# analog-encoder.net
KiCad netlist of a schematic drawn in Altium Designer
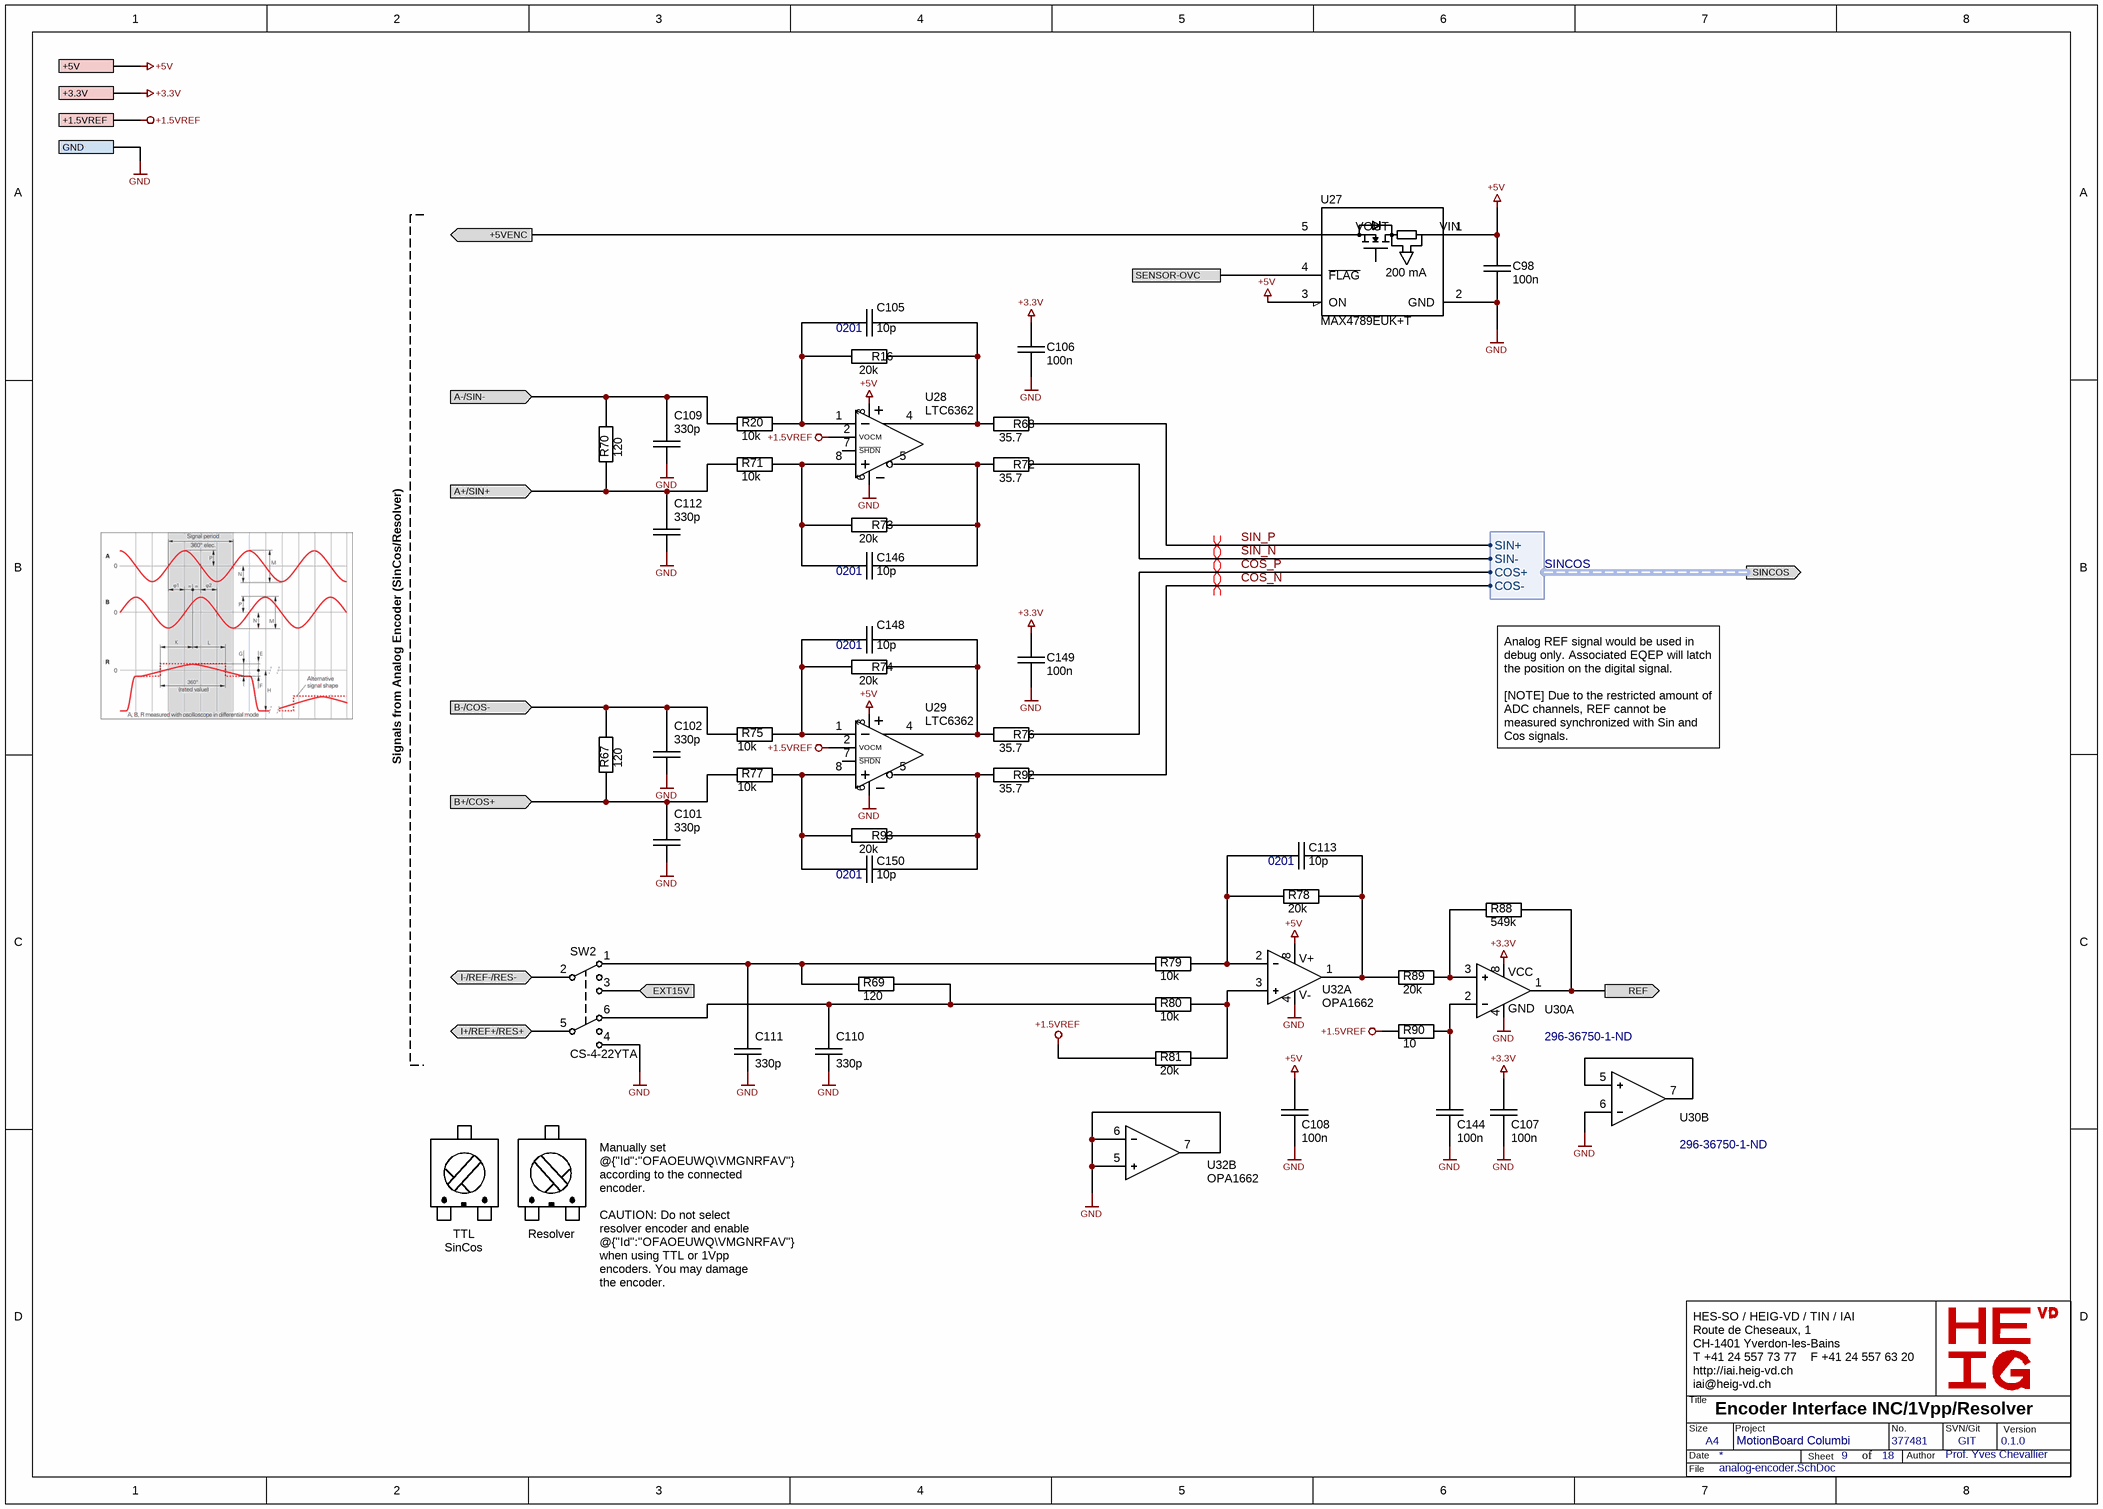
[diagram p0: analog-encoder.SchDoc]

(export (version "E")
  (design (tool "Eeschema 10.0.6"))
  (components
    (comp (ref "C98")
      (value "100n")
      (footprint "SM/C0402")
      (description "100 nF ±10% 25V Ceramic Capacitor X5R 0402 (1005 Metric)")
      (fields (field (name "VOLTAGE") "25V"))
      (libsource (lib "motionboard") (part "CAP CER 100NF 25V X5R 0402"))
    )
    (comp (ref "C101")
      (value "330p")
      (footprint "SM/C0402")
      (description "330 pF ±5% 50V Ceramic Capacitor C0G, NP0 0402 (1005 Metric)")
      (fields (field (name "VOLTAGE") "50V"))
      (libsource (lib "motionboard") (part "CAP CER 330PF 50V C0G/NP0 0402"))
    )
    (comp (ref "C102")
      (value "330p")
      (footprint "SM/C0402")
      (description "330 pF ±5% 50V Ceramic Capacitor C0G, NP0 0402 (1005 Metric)")
      (fields (field (name "VOLTAGE") "50V"))
      (libsource (lib "motionboard") (part "CAP CER 330PF 50V C0G/NP0 0402"))
    )
    (comp (ref "C105")
      (value "10p")
      (footprint "SM/C0201")
      (description "10 pF ±5% 25V Ceramic Capacitor C0G, NP0 0201 (0603 Metric)")
      (fields (field (name "VOLTAGE") "25V") (field (name "CASE") "0201"))
      (libsource (lib "motionboard") (part "CAP CER 10PF 25V C0G/NP0 0201"))
    )
    (comp (ref "C106")
      (value "100n")
      (footprint "SM/C0402")
      (description "100 nF ±10% 25V Ceramic Capacitor X5R 0402 (1005 Metric)")
      (fields (field (name "VOLTAGE") "25V"))
      (libsource (lib "motionboard") (part "CAP CER 100NF 25V X5R 0402"))
    )
    (comp (ref "C107")
      (value "100n")
      (footprint "SM/C0402")
      (description "100 nF ±10% 25V Ceramic Capacitor X5R 0402 (1005 Metric)")
      (fields (field (name "VOLTAGE") "25V"))
      (libsource (lib "motionboard") (part "CAP CER 100NF 25V X5R 0402"))
    )
    (comp (ref "C108")
      (value "100n")
      (footprint "SM/C0402")
      (description "100 nF ±10% 25V Ceramic Capacitor X5R 0402 (1005 Metric)")
      (fields (field (name "VOLTAGE") "25V"))
      (libsource (lib "motionboard") (part "CAP CER 100NF 25V X5R 0402"))
    )
    (comp (ref "C109")
      (value "330p")
      (footprint "SM/C0402")
      (description "330 pF ±5% 50V Ceramic Capacitor C0G, NP0 0402 (1005 Metric)")
      (fields (field (name "VOLTAGE") "50V"))
      (libsource (lib "motionboard") (part "CAP CER 330PF 50V C0G/NP0 0402"))
    )
    (comp (ref "C110")
      (value "330p")
      (footprint "SM/C0402")
      (description "330 pF ±5% 50V Ceramic Capacitor C0G, NP0 0402 (1005 Metric)")
      (fields (field (name "VOLTAGE") "50V"))
      (libsource (lib "motionboard") (part "CAP CER 330PF 50V C0G/NP0 0402"))
    )
    (comp (ref "C111")
      (value "330p")
      (footprint "SM/C0402")
      (description "330 pF ±5% 50V Ceramic Capacitor C0G, NP0 0402 (1005 Metric)")
      (fields (field (name "VOLTAGE") "50V"))
      (libsource (lib "motionboard") (part "CAP CER 330PF 50V C0G/NP0 0402"))
    )
    (comp (ref "C112")
      (value "330p")
      (footprint "SM/C0402")
      (description "330 pF ±5% 50V Ceramic Capacitor C0G, NP0 0402 (1005 Metric)")
      (fields (field (name "VOLTAGE") "50V"))
      (libsource (lib "motionboard") (part "CAP CER 330PF 50V C0G/NP0 0402"))
    )
    (comp (ref "C113")
      (value "10p")
      (footprint "SM/C0201")
      (description "10 pF ±5% 25V Ceramic Capacitor C0G, NP0 0201 (0603 Metric)")
      (fields (field (name "VOLTAGE") "25V") (field (name "CASE") "0201"))
      (libsource (lib "motionboard") (part "CAP CER 10PF 25V C0G/NP0 0201"))
    )
    (comp (ref "C144")
      (value "100n")
      (footprint "SM/C0402")
      (description "100 nF ±10% 25V Ceramic Capacitor X5R 0402 (1005 Metric)")
      (fields (field (name "VOLTAGE") "25V"))
      (libsource (lib "motionboard") (part "CAP CER 100NF 25V X5R 0402"))
    )
    (comp (ref "C146")
      (value "10p")
      (footprint "SM/C0201")
      (description "10 pF ±5% 25V Ceramic Capacitor C0G, NP0 0201 (0603 Metric)")
      (fields (field (name "VOLTAGE") "25V") (field (name "CASE") "0201"))
      (libsource (lib "motionboard") (part "CAP CER 10PF 25V C0G/NP0 0201"))
    )
    (comp (ref "C148")
      (value "10p")
      (footprint "SM/C0201")
      (description "10 pF ±5% 25V Ceramic Capacitor C0G, NP0 0201 (0603 Metric)")
      (fields (field (name "VOLTAGE") "25V") (field (name "CASE") "0201"))
      (libsource (lib "motionboard") (part "CAP CER 10PF 25V C0G/NP0 0201"))
    )
    (comp (ref "C149")
      (value "100n")
      (footprint "SM/C0402")
      (description "100 nF ±10% 25V Ceramic Capacitor X5R 0402 (1005 Metric)")
      (fields (field (name "VOLTAGE") "25V"))
      (libsource (lib "motionboard") (part "CAP CER 100NF 25V X5R 0402"))
    )
    (comp (ref "C150")
      (value "10p")
      (footprint "SM/C0201")
      (description "10 pF ±5% 25V Ceramic Capacitor C0G, NP0 0201 (0603 Metric)")
      (fields (field (name "VOLTAGE") "25V") (field (name "CASE") "0201"))
      (libsource (lib "motionboard") (part "CAP CER 10PF 25V C0G/NP0 0201"))
    )
    (comp (ref "R16")
      (value "20k")
      (footprint "SM/R0402")
      (description "20 kOhms ±1% 0.063W, 1/16W Chip Resistor 0402 (1005 Metric) Moisture Resistant Thick Film")
      (libsource (lib "motionboard") (part "RES 20K OHM 1% 1/16W 0402"))
    )
    (comp (ref "R20")
      (value "10k")
      (footprint "SM/R0402")
      (description "10 kOhms ±1% 0.063W, 1/16W Chip Resistor 0402 (1005 Metric) Moisture Resistant Thick Film")
      (libsource (lib "motionboard") (part "RES 10K OHM 1% 1/16W 0402"))
    )
    (comp (ref "R67")
      (value "120")
      (footprint "SM/R0402")
      (description "120 Ohms ±1% 0.063W, 1/16W Chip Resistor 0402 (1005 Metric) Moisture Resistant Thick Film")
      (libsource (lib "motionboard") (part "RES 120 OHM 1% 1/16W 0402"))
    )
    (comp (ref "R68")
      (value "35.7")
      (footprint "SM/R0402")
      (description "20 kOhms ±1% 0.063W, 1/16W Chip Resistor 0402 (1005 Metric) Moisture Resistant Thick Film")
      (libsource (lib "motionboard") (part "RES 20K OHM 1% 1/16W 0402"))
    )
    (comp (ref "R69")
      (value "120")
      (footprint "SM/R0402")
      (description "120 Ohms ±1% 0.063W, 1/16W Chip Resistor 0402 (1005 Metric) Moisture Resistant Thick Film")
      (libsource (lib "") (part "RES 120 OHM 1% 1/16W 0402_1"))
    )
    (comp (ref "R70")
      (value "120")
      (footprint "SM/R0402")
      (description "120 Ohms ±1% 0.063W, 1/16W Chip Resistor 0402 (1005 Metric) Moisture Resistant Thick Film")
      (libsource (lib "motionboard") (part "RES 120 OHM 1% 1/16W 0402"))
    )
    (comp (ref "R71")
      (value "10k")
      (footprint "SM/R0402")
      (description "10 kOhms ±1% 0.063W, 1/16W Chip Resistor 0402 (1005 Metric) Moisture Resistant Thick Film")
      (libsource (lib "motionboard") (part "RES 10K OHM 1% 1/16W 0402"))
    )
    (comp (ref "R72")
      (value "35.7")
      (footprint "SM/R0402")
      (description "20 kOhms ±1% 0.063W, 1/16W Chip Resistor 0402 (1005 Metric) Moisture Resistant Thick Film")
      (libsource (lib "motionboard") (part "RES 20K OHM 1% 1/16W 0402"))
    )
    (comp (ref "R73")
      (value "20k")
      (footprint "SM/R0402")
      (description "20 kOhms ±1% 0.063W, 1/16W Chip Resistor 0402 (1005 Metric) Moisture Resistant Thick Film")
      (libsource (lib "motionboard") (part "RES 20K OHM 1% 1/16W 0402"))
    )
    (comp (ref "R74")
      (value "20k")
      (footprint "SM/R0402")
      (description "20 kOhms ±1% 0.063W, 1/16W Chip Resistor 0402 (1005 Metric) Moisture Resistant Thick Film")
      (libsource (lib "motionboard") (part "RES 20K OHM 1% 1/16W 0402"))
    )
    (comp (ref "R75")
      (value "10k")
      (footprint "SM/R0402")
      (description "10 kOhms ±1% 0.063W, 1/16W Chip Resistor 0402 (1005 Metric) Moisture Resistant Thick Film")
      (libsource (lib "motionboard") (part "RES 10K OHM 1% 1/16W 0402"))
    )
    (comp (ref "R76")
      (value "35.7")
      (footprint "SM/R0402")
      (description "20 kOhms ±1% 0.063W, 1/16W Chip Resistor 0402 (1005 Metric) Moisture Resistant Thick Film")
      (libsource (lib "motionboard") (part "RES 20K OHM 1% 1/16W 0402"))
    )
    (comp (ref "R77")
      (value "10k")
      (footprint "SM/R0402")
      (description "10 kOhms ±1% 0.063W, 1/16W Chip Resistor 0402 (1005 Metric) Moisture Resistant Thick Film")
      (libsource (lib "motionboard") (part "RES 10K OHM 1% 1/16W 0402"))
    )
    (comp (ref "R78")
      (value "20k")
      (footprint "SM/R0402")
      (description "20 kOhms ±1% 0.063W, 1/16W Chip Resistor 0402 (1005 Metric) Moisture Resistant Thick Film")
      (libsource (lib "motionboard") (part "RES 20K OHM 1% 1/16W 0402"))
    )
    (comp (ref "R79")
      (value "10k")
      (footprint "SM/R0402")
      (description "10 kOhms ±1% 0.063W, 1/16W Chip Resistor 0402 (1005 Metric) Moisture Resistant Thick Film")
      (libsource (lib "motionboard") (part "RES 10K OHM 1% 1/16W 0402"))
    )
    (comp (ref "R80")
      (value "10k")
      (footprint "SM/R0402")
      (description "10 kOhms ±1% 0.063W, 1/16W Chip Resistor 0402 (1005 Metric) Moisture Resistant Thick Film")
      (libsource (lib "motionboard") (part "RES 10K OHM 1% 1/16W 0402"))
    )
    (comp (ref "R81")
      (value "20k")
      (footprint "SM/R0402")
      (description "20 kOhms ±1% 0.063W, 1/16W Chip Resistor 0402 (1005 Metric) Moisture Resistant Thick Film")
      (libsource (lib "motionboard") (part "RES 20K OHM 1% 1/16W 0402"))
    )
    (comp (ref "R88")
      (value "549k")
      (footprint "SM/R0402")
      (description "20 kOhms ±1% 0.063W, 1/16W Chip Resistor 0402 (1005 Metric) Moisture Resistant Thick Film")
      (libsource (lib "motionboard") (part "RES 20K OHM 1% 1/16W 0402"))
    )
    (comp (ref "R89")
      (value "20k")
      (footprint "SM/R0402")
      (description "20 kOhms ±1% 0.063W, 1/16W Chip Resistor 0402 (1005 Metric) Moisture Resistant Thick Film")
      (libsource (lib "motionboard") (part "RES 20K OHM 1% 1/16W 0402"))
    )
    (comp (ref "R90")
      (value "10")
      (footprint "SM/R0402")
      (description "20 kOhms ±1% 0.063W, 1/16W Chip Resistor 0402 (1005 Metric) Moisture Resistant Thick Film")
      (libsource (lib "motionboard") (part "RES 20K OHM 1% 1/16W 0402"))
    )
    (comp (ref "R92")
      (value "35.7")
      (footprint "SM/R0402")
      (description "20 kOhms ±1% 0.063W, 1/16W Chip Resistor 0402 (1005 Metric) Moisture Resistant Thick Film")
      (libsource (lib "motionboard") (part "RES 20K OHM 1% 1/16W 0402"))
    )
    (comp (ref "R93")
      (value "20k")
      (footprint "SM/R0402")
      (description "20 kOhms ±1% 0.063W, 1/16W Chip Resistor 0402 (1005 Metric) Moisture Resistant Thick Film")
      (libsource (lib "motionboard") (part "RES 20K OHM 1% 1/16W 0402"))
    )
    (comp (ref "SW2")
      (value "CS-4-22YTA")
      (footprint "CS-4-22YA")
      (description "Dip Switch DPDT 2 Position Surface Mount Rotary for Tool Actuator 100mA 16VDC")
      (libsource (lib "motionboard") (part "CS-4-22YTA"))
    )
    (comp (ref "U27")
      (value "MAX4789EUK+T")
      (footprint "SOT23-5")
      (description "Current Limiting Regulator 200mA SOT-23-5")
      (fields (field (name "VOLTAGE") "2.3..5.5V"))
      (libsource (lib "motionboard") (part "MAX4789"))
    )
    (comp (ref "U28") (value "LTC6362") (libsource (lib "motionboard") (part "LTC6362")))
    (comp (ref "U29") (value "LTC6362") (libsource (lib "motionboard") (part "LTC6362")))
    (comp (ref "U30")
      (value "~")
      (description "Comparator General Purpose Push-Pull SOT-23-5\r\nIC COMPARATOR RRI SGL SOT23-5")
      (fields (field (name "SUPPLIER PART NUMBER 1") "296-36750-1-ND"))
      (libsource (lib "motionboard") (part "TLV3201"))
    )
    (comp (ref "U32")
      (value "OPA1662")
      (footprint "SOIC8")
      (description "Dual operational amplifier")
      (libsource (lib "motionboard") (part "OPA1662"))
    )
  )
  (nets
    (net (code "2") (name "+1.5VREF") (class "Default")
      (node (ref "R81") (pin "2") (pintype "passive"))
      (node (ref "R90") (pin "2") (pintype "passive"))
      (node (ref "U28") (pin "2") (pinfunction "VOCM_2") (pintype "passive"))
      (node (ref "U29") (pin "2") (pinfunction "VOCM_2") (pintype "passive"))
    )
    (net (code "3") (name "+3.3V") (class "Default")
      (node (ref "C106") (pin "2") (pintype "passive"))
      (node (ref "C107") (pin "2") (pintype "passive"))
      (node (ref "C149") (pin "2") (pintype "passive"))
      (node (ref "U30") (pin "8") (pinfunction "V+_8") (pintype "passive"))
    )
    (net (code "4") (name "+5V") (class "Default")
      (node (ref "C108") (pin "2") (pintype "passive"))
      (node (ref "C98") (pin "1") (pintype "passive"))
      (node (ref "U27") (pin "1") (pinfunction "VIN_1") (pintype "passive"))
      (node (ref "U27") (pin "3") (pinfunction "ON_3") (pintype "passive"))
      (node (ref "U28") (pin "3") (pinfunction "V+_3") (pintype "passive"))
      (node (ref "U29") (pin "3") (pinfunction "V+_3") (pintype "passive"))
      (node (ref "U32") (pin "8") (pinfunction "V+_8") (pintype "passive"))
    )
    (net (code "5") (name "/+5VENC") (class "Default")
      (node (ref "U27") (pin "5") (pinfunction "VOUT_5") (pintype "passive"))
    )
    (net (code "6") (name "/A+{slash}SIN+") (class "Default")
      (node (ref "C112") (pin "1") (pintype "passive"))
      (node (ref "R70") (pin "2") (pintype "passive"))
      (node (ref "R71") (pin "2") (pintype "passive"))
    )
    (net (code "7") (name "/A-{slash}SIN-") (class "Default")
      (node (ref "C109") (pin "1") (pintype "passive"))
      (node (ref "R20") (pin "2") (pintype "passive"))
      (node (ref "R70") (pin "1") (pintype "passive"))
    )
    (net (code "8") (name "/B+{slash}COS+") (class "Default")
      (node (ref "C101") (pin "1") (pintype "passive"))
      (node (ref "R67") (pin "2") (pintype "passive"))
      (node (ref "R77") (pin "2") (pintype "passive"))
    )
    (net (code "9") (name "/B-{slash}COS-") (class "Default")
      (node (ref "C102") (pin "1") (pintype "passive"))
      (node (ref "R67") (pin "1") (pintype "passive"))
      (node (ref "R75") (pin "2") (pintype "passive"))
    )
    (net (code "10") (name "/COS_N") (class "Default") (node (ref "R92") (pin "1") (pintype "passive")))
    (net (code "11") (name "/COS_P") (class "Default") (node (ref "R76") (pin "1") (pintype "passive")))
    (net (code "12") (name "/EXT15V") (class "Default")
      (node (ref "SW2") (pin "3") (pinfunction "1A_3") (pintype "passive"))
    )
    (net (code "13") (name "/I+{slash}REF+{slash}RES+") (class "Default")
      (node (ref "SW2") (pin "5") (pinfunction "CB_5") (pintype "passive"))
    )
    (net (code "14") (name "/I-{slash}REF-{slash}RES-") (class "Default")
      (node (ref "SW2") (pin "2") (pinfunction "CA_2") (pintype "passive"))
    )
    (net (code "15") (name "/REF") (class "Default")
      (node (ref "R88") (pin "1") (pintype "passive"))
      (node (ref "U30") (pin "1") (pinfunction "OUT_1") (pintype "passive"))
    )
    (net (code "16") (name "/SENSOR-OVC") (class "Default")
      (node (ref "U27") (pin "4") (pinfunction "~{FLAG}_4") (pintype "passive"))
    )
    (net (code "17") (name "/SIN_N") (class "Default") (node (ref "R72") (pin "1") (pintype "passive")))
    (net (code "18") (name "/SIN_P") (class "Default") (node (ref "R68") (pin "1") (pintype "passive")))
    (net (code "20") (name "GND") (class "Default")
      (node (ref "C101") (pin "2") (pintype "passive"))
      (node (ref "C102") (pin "2") (pintype "passive"))
      (node (ref "C106") (pin "1") (pintype "passive"))
      (node (ref "C107") (pin "1") (pintype "passive"))
      (node (ref "C108") (pin "1") (pintype "passive"))
      (node (ref "C109") (pin "2") (pintype "passive"))
      (node (ref "C110") (pin "2") (pintype "passive"))
      (node (ref "C111") (pin "2") (pintype "passive"))
      (node (ref "C112") (pin "2") (pintype "passive"))
      (node (ref "C144") (pin "1") (pintype "passive"))
      (node (ref "C149") (pin "1") (pintype "passive"))
      (node (ref "C98") (pin "2") (pintype "passive"))
      (node (ref "SW2") (pin "4") (pinfunction "2B_4") (pintype "passive"))
      (node (ref "U27") (pin "2") (pinfunction "GND_2") (pintype "passive"))
      (node (ref "U28") (pin "6") (pinfunction "V+_6") (pintype "passive"))
      (node (ref "U29") (pin "6") (pinfunction "V+_6") (pintype "passive"))
      (node (ref "U30") (pin "4") (pinfunction "GND_4") (pintype "passive"))
      (node (ref "U30") (pin "6") (pinfunction "IN-_6") (pintype "passive"))
      (node (ref "U32") (pin "4") (pinfunction "V-_4") (pintype "passive"))
      (node (ref "U32") (pin "5") (pinfunction "IN+_5") (pintype "passive"))
      (node (ref "U32") (pin "6") (pinfunction "IN-_6") (pintype "passive"))
      (node (ref "U32") (pin "7") (pinfunction "OUT_7") (pintype "passive"))
    )
    (net (code "21") (name "Net-(SW2-1B)") (class "Default")
      (node (ref "C110") (pin "1") (pintype "passive"))
      (node (ref "R69") (pin "1") (pintype "passive"))
      (node (ref "R80") (pin "2") (pintype "passive"))
      (node (ref "SW2") (pin "6") (pinfunction "1B_6") (pintype "passive"))
    )
    (net (code "22") (name "Net-(SW2-2A)") (class "Default")
      (node (ref "C111") (pin "1") (pintype "passive"))
      (node (ref "R69") (pin "2") (pintype "passive"))
      (node (ref "R79") (pin "2") (pintype "passive"))
      (node (ref "SW2") (pin "1") (pinfunction "2A_1") (pintype "passive"))
    )
    (net (code "23") (name "Net-(U28-IN+)") (class "Default")
      (node (ref "C146") (pin "2") (pintype "passive"))
      (node (ref "R71") (pin "1") (pintype "passive"))
      (node (ref "R73") (pin "2") (pintype "passive"))
      (node (ref "U28") (pin "8") (pinfunction "IN+_8") (pintype "passive"))
    )
    (net (code "24") (name "Net-(U28-IN-)") (class "Default")
      (node (ref "C105") (pin "2") (pintype "passive"))
      (node (ref "R16") (pin "2") (pintype "passive"))
      (node (ref "R20") (pin "1") (pintype "passive"))
      (node (ref "U28") (pin "1") (pinfunction "IN-_1") (pintype "passive"))
    )
    (net (code "25") (name "Net-(U28-OUT+)") (class "Default")
      (node (ref "C105") (pin "1") (pintype "passive"))
      (node (ref "R16") (pin "1") (pintype "passive"))
      (node (ref "R68") (pin "2") (pintype "passive"))
      (node (ref "U28") (pin "4") (pinfunction "OUT+_4") (pintype "passive"))
    )
    (net (code "26") (name "Net-(U28-OUT-)") (class "Default")
      (node (ref "C146") (pin "1") (pintype "passive"))
      (node (ref "R72") (pin "2") (pintype "passive"))
      (node (ref "R73") (pin "1") (pintype "passive"))
      (node (ref "U28") (pin "5") (pinfunction "OUT-_5") (pintype "passive"))
    )
    (net (code "27") (name "Net-(U29-IN+)") (class "Default")
      (node (ref "C150") (pin "2") (pintype "passive"))
      (node (ref "R77") (pin "1") (pintype "passive"))
      (node (ref "R93") (pin "2") (pintype "passive"))
      (node (ref "U29") (pin "8") (pinfunction "IN+_8") (pintype "passive"))
    )
    (net (code "28") (name "Net-(U29-IN-)") (class "Default")
      (node (ref "C148") (pin "2") (pintype "passive"))
      (node (ref "R74") (pin "2") (pintype "passive"))
      (node (ref "R75") (pin "1") (pintype "passive"))
      (node (ref "U29") (pin "1") (pinfunction "IN-_1") (pintype "passive"))
    )
    (net (code "29") (name "Net-(U29-OUT+)") (class "Default")
      (node (ref "C148") (pin "1") (pintype "passive"))
      (node (ref "R74") (pin "1") (pintype "passive"))
      (node (ref "R76") (pin "2") (pintype "passive"))
      (node (ref "U29") (pin "4") (pinfunction "OUT+_4") (pintype "passive"))
    )
    (net (code "30") (name "Net-(U29-OUT-)") (class "Default")
      (node (ref "C150") (pin "1") (pintype "passive"))
      (node (ref "R92") (pin "2") (pintype "passive"))
      (node (ref "R93") (pin "1") (pintype "passive"))
      (node (ref "U29") (pin "5") (pinfunction "OUT-_5") (pintype "passive"))
    )
    (net (code "31") (name "Net-(U30A-IN+)") (class "Default")
      (node (ref "R88") (pin "2") (pintype "passive"))
      (node (ref "R89") (pin "1") (pintype "passive"))
      (node (ref "U30") (pin "3") (pinfunction "IN+_3") (pintype "passive"))
    )
    (net (code "32") (name "Net-(U30A-IN-)") (class "Default")
      (node (ref "C144") (pin "2") (pintype "passive"))
      (node (ref "R90") (pin "1") (pintype "passive"))
      (node (ref "U30") (pin "2") (pinfunction "IN-_2") (pintype "passive"))
    )
    (net (code "33") (name "Net-(U30B-IN+)") (class "Default")
      (node (ref "U30") (pin "5") (pinfunction "IN+_5") (pintype "passive"))
      (node (ref "U30") (pin "7") (pinfunction "OUT_7") (pintype "passive"))
    )
    (net (code "34") (name "Net-(U32A-IN+)") (class "Default")
      (node (ref "R80") (pin "1") (pintype "passive"))
      (node (ref "R81") (pin "1") (pintype "passive"))
      (node (ref "U32") (pin "3") (pinfunction "IN+_3") (pintype "passive"))
    )
    (net (code "35") (name "Net-(U32A-IN-)") (class "Default")
      (node (ref "C113") (pin "2") (pintype "passive"))
      (node (ref "R78") (pin "2") (pintype "passive"))
      (node (ref "R79") (pin "1") (pintype "passive"))
      (node (ref "U32") (pin "2") (pinfunction "IN-_2") (pintype "passive"))
    )
    (net (code "36") (name "Net-(U32A-OUT)") (class "Default")
      (node (ref "C113") (pin "1") (pintype "passive"))
      (node (ref "R78") (pin "1") (pintype "passive"))
      (node (ref "R89") (pin "2") (pintype "passive"))
      (node (ref "U32") (pin "1") (pinfunction "OUT_1") (pintype "passive"))
    )
    (net (code "37") (name "unconnected-(U28-~{SHDN}-Pad7)") (class "Default")
      (node (ref "U28") (pin "7") (pinfunction "~{SHDN}_7") (pintype "passive"))
    )
    (net (code "38") (name "unconnected-(U29-~{SHDN}-Pad7)") (class "Default")
      (node (ref "U29") (pin "7") (pinfunction "~{SHDN}_7") (pintype "passive"))
    )
  )
)
